# BuckConverter_D14.net
KiCad netlist of a schematic drawn in Altium Designer
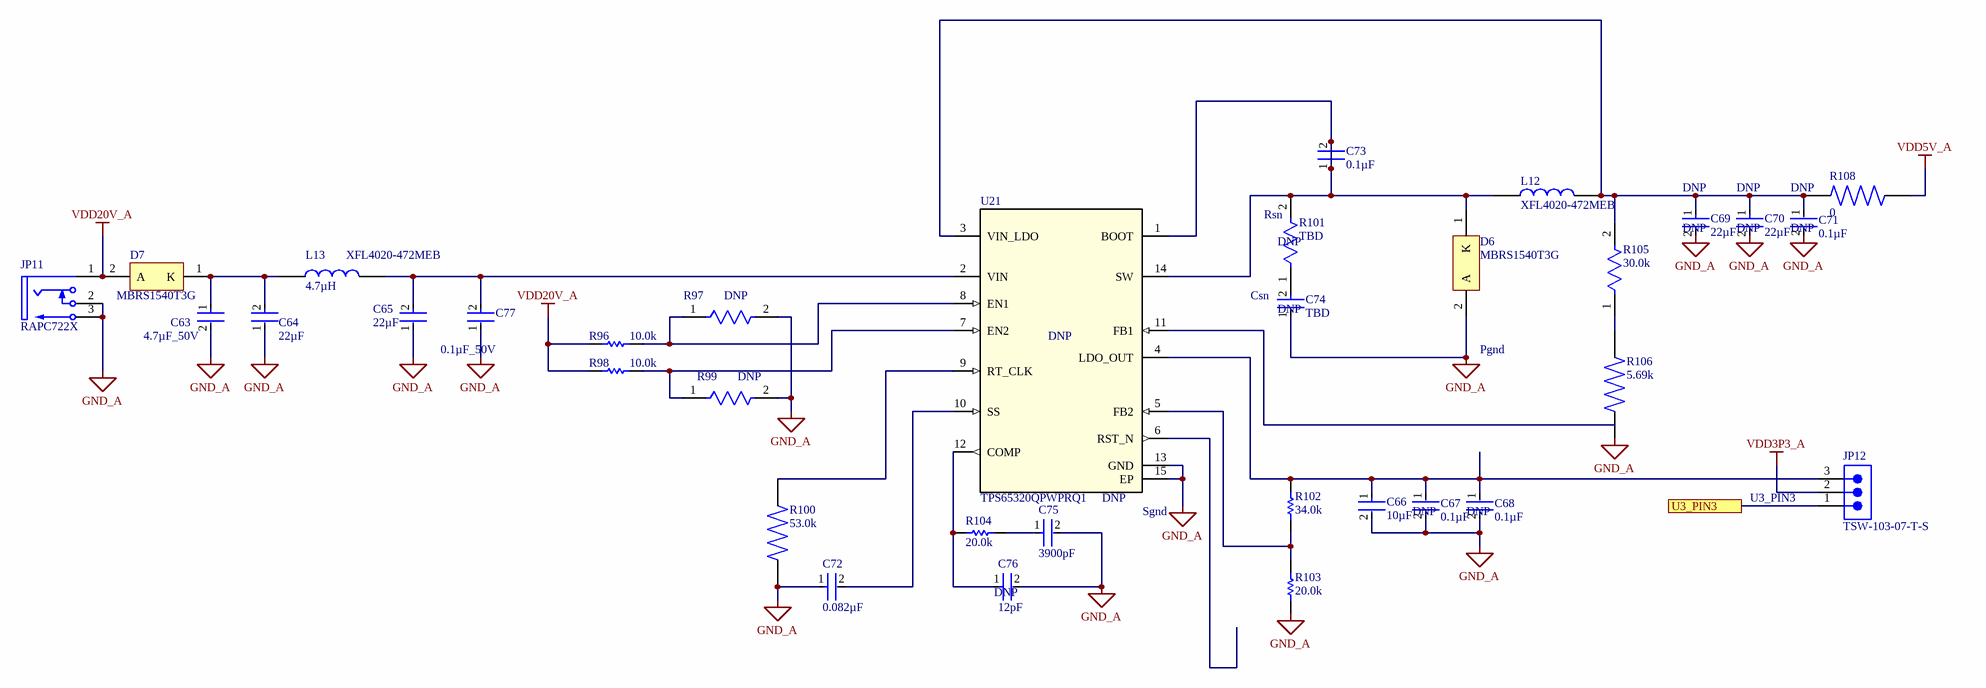
[diagram p0: BuckConverter_D14.SchDoc]

(export (version "E")
  (design (tool "Eeschema 10.0.6"))
  (components
    (comp (ref "C63")
      (value "4.7µF_50V")
      (footprint "FP-C2012-125-0_2-MFG")
      (description "Multilayer Ceramic Capacitors 10μF ±10% 10V X7R SMD 0805")
      (fields (field (name "TOLERANCE") "10%") (field (name "VOLTAGE") "10V"))
      (libsource (lib "Altium Content Vault") (part "b4654b650e69147ec39a6b967a45e02"))
    )
    (comp (ref "C64")
      (value "22µF")
      (footprint "FP-GRM15-MFG")
      (description "CAP CER 0.1UF 16V X7R 0402")
      (fields (field (name "MANUFACTURER PART NUMBER") "GRM155R71C104KA88D") (field (name "TOLERANCE") "10%"))
      (libsource (lib "Altium Content Vault") (part "236180d848d6139a670b325ea6854c9"))
    )
    (comp (ref "C65")
      (value "22µF")
      (footprint "FP-GRM15-MFG")
      (description "CAP CER 0.1UF 16V X7R 0402")
      (fields (field (name "MANUFACTURER PART NUMBER") "GRM155R71C104KA88D") (field (name "TOLERANCE") "10%"))
      (libsource (lib "Altium Content Vault") (part "236180d848d6139a670b325ea6854c9"))
    )
    (comp (ref "C66")
      (value "10µF")
      (footprint "FP-C2012-125-0_2-MFG")
      (description "Multilayer Ceramic Capacitors 10μF ±10% 10V X7R SMD 0805")
      (fields (field (name "TOLERANCE") "10%") (field (name "VOLTAGE") "10V"))
      (libsource (lib "Altium Content Vault") (part "b4654b650e69147ec39a6b967a45e02"))
    )
    (comp (ref "C67")
      (value "0.1µF")
      (footprint "FP-GRM15-MFG")
      (description "CAP CER 0.1UF 16V X7R 0402")
      (fields (field (name "MANUFACTURER PART NUMBER") "GRM155R71C104KA88D") (field (name "TOLERANCE") "10%"))
      (libsource (lib "Altium Content Vault") (part "236180d848d6139a670b325ea6854c9"))
    )
    (comp (ref "C68")
      (value "0.1µF")
      (footprint "FP-GRM15-MFG")
      (description "CAP CER 0.1UF 16V X7R 0402")
      (fields (field (name "MANUFACTURER PART NUMBER") "GRM155R71C104KA88D") (field (name "TOLERANCE") "10%"))
      (libsource (lib "Altium Content Vault") (part "236180d848d6139a670b325ea6854c9"))
    )
    (comp (ref "C69")
      (value "22µF")
      (footprint "FP-C3216-160-0_2-IPC_B")
      (description "Multilayer Ceramic Capacitors 22uF ±20% 25V X5R SMD 1206")
      (fields (field (name "TOLERANCE") "20%"))
      (libsource (lib "Altium Content Vault") (part "11868f565c42a9108669ba33697ecf6"))
    )
    (comp (ref "C70")
      (value "22µF")
      (footprint "FP-C3216-160-0_2-IPC_B")
      (description "Multilayer Ceramic Capacitors 22uF ±20% 25V X5R SMD 1206")
      (fields (field (name "TOLERANCE") "20%"))
      (libsource (lib "Altium Content Vault") (part "11868f565c42a9108669ba33697ecf6"))
    )
    (comp (ref "C71")
      (value "0.1µF")
      (footprint "FP-GRM15-MFG")
      (description "CAP CER 0.1UF 16V X7R 0402")
      (fields (field (name "MANUFACTURER PART NUMBER") "GRM155R71C104KA88D") (field (name "TOLERANCE") "10%"))
      (libsource (lib "Altium Content Vault") (part "236180d848d6139a670b325ea6854c9"))
    )
    (comp (ref "C72")
      (value "0.082µF")
      (footprint "FP-C0402-BB-MFG")
      (description "C0402 82,000 pF X7R 10.00% 16 V")
      (fields
        (field (name "OCTOPART") "https://octopart.com/c0402c823k4ractu-kemet-134782")
        (field (name "MANUFACTURER") "Kemet")
      )
      (libsource (lib "Altium Content Vault") (part "b4654b650e69147ec39a6b967a45e02"))
    )
    (comp (ref "C73")
      (value "0.1µF")
      (footprint "FP-GRM15-MFG")
      (description "CAP CER 0.1UF 16V X7R 0402")
      (fields (field (name "MANUFACTURER PART NUMBER") "GRM155R71C104KA88D") (field (name "TOLERANCE") "10%"))
      (libsource (lib "Altium Content Vault") (part "236180d848d6139a670b325ea6854c9"))
    )
    (comp (ref "C74")
      (value "TBD")
      (footprint "FP-GRM15-MFG")
      (description "CAP CER 0.1UF 16V X7R 0402")
      (fields (field (name "MANUFACTURER PART NUMBER") "GRM155R71C104KA88D") (field (name "TOLERANCE") "10%"))
      (libsource (lib "Altium Content Vault") (part "236180d848d6139a670b325ea6854c9"))
    )
    (comp (ref "C75")
      (value "3900pF")
      (footprint "FP-C0402-BB-MFG")
      (description "CAP CER 3900PF 16V X7R 0402")
      (fields
        (field (name "MANUFACTURER PART NUMBER") "C0402C392K4RACTU")
        (field (name "OCTOPART") "https://octopart.com/c0402c392k4ractu-kemet-12577363")
      )
      (libsource (lib "Altium Content Vault") (part "b4654b650e69147ec39a6b967a45e02"))
    )
    (comp (ref "C76")
      (value "12pF")
      (footprint "FP-C0402-BB-MFG")
      (description "CAP CER 12PF 25V C0G/NP0 0402")
      (fields
        (field (name "OCTOPART") "https://octopart.com/c0402c120j3gacauto-kemet-21768529")
        (field (name "MANUFACTURER PART NUMBER") "C0402C120J3GACAUTO")
      )
      (libsource (lib "Altium Content Vault") (part "b4654b650e69147ec39a6b967a45e02"))
    )
    (comp (ref "C77")
      (value "0.1µF_50V")
      (footprint "FP-C1608-080-0_1-IPC_B")
      (description "Multilayer Ceramic Capacitors 100nF ±10% 50V X7R SMD 0603")
      (fields (field (name "VOLTAGE") "50V") (field (name "TOLERANCE") "10%"))
      (libsource (lib "Altium Content Vault") (part "236180d848d6139a670b325ea6854c9"))
    )
    (comp (ref "D6")
      (value "MBRS1540T3G")
      (footprint "ONSC-SMB-2-403A-03_E_V")
      (description "Schottky Power Rectifier, 2-Pin SMB, Pb-Free, Tape and Reel")
      (fields (field (name "MANUFACTURER") "On Semiconductor"))
      (libsource (lib "") (part "ONSC-D-K1A2-2_A_1"))
    )
    (comp (ref "D7")
      (value "MBRS1540T3G")
      (footprint "ONSC-SMB-2-403A-03_E_V")
      (description "Schottky Power Rectifier, 2-Pin SMB, Pb-Free, Tape and Reel")
      (fields (field (name "MANUFACTURER") "On Semiconductor"))
      (libsource (lib "Altium Content Vault") (part "ONSC-D-K1A2-2_A"))
    )
    (comp (ref "JP11")
      (value "RAPC722X")
      (footprint "SWITCH-RAPC712X-3_V")
      (description "Power Jack, 5 A, 3-Pin THD, RoHS, Bulk")
      (fields (field (name "MANUFACTURER") "Switchcraft"))
      (libsource (lib "Altium Content Vault") (part "SWITCH-RAPC712X-3"))
    )
    (comp (ref "JP12")
      (value "TSW-103-07-T-S")
      (footprint "SMTC-TSW-103-07-X-S")
      (description "0.025\" SQ Post Header, Through-hole, Vertical, -55 to 105 degC, 2.54 mm Pitch, 3-Pin, Male, RoHS")
      (fields (field (name "MANUFACTURER") "Samtec"))
      (libsource (lib "Altium Content Vault") (part "SMTC-TSW-103-X-X-S-X"))
    )
    (comp (ref "L12")
      (value "XFL4020-472MEB")
      (footprint "XFL4020472MEB")
      (description "Fixed Inductors 4.7uH 20% 5A 57.4mOhms AEC-Q200")
      (fields (field (name "MOUSER PART NUMBER") "994-XFL4020-472MEB"))
      (libsource (lib "XFL4020-472MEB") (part "XFL4020-472MEB"))
    )
    (comp (ref "L13")
      (value "4.7µH")
      (footprint "XFL4020472MEB")
      (description "Fixed Inductors 4.7uH 20% 5A 57.4mOhms AEC-Q200")
      (fields
        (field (name "MANUFACTURER_PART_NUMBER") "XFL4020-472MEB")
        (field (name "MOUSER PART NUMBER") "994-XFL4020-472MEB")
      )
      (libsource (lib "XFL4020-472MEB") (part "XFL4020-472MEB"))
    )
    (comp (ref "R96")
      (value "10.0k")
      (footprint "RESC1609X55X30LL15T15")
      (description "Chip Resistor, 10 KOhm, +/- 1%, 0.1 W, -55 to 155 degC, 0603 (1608 Metric), RoHS, Tape and Reel")
      (fields (field (name "TOLERANCE") "1%") (field (name "MANUFACTURER") "Panasonic"))
      (libsource (lib "Altium Content Vault") (part "RES-2"))
    )
    (comp (ref "R97")
      (value "DNP")
      (footprint "FP-ERJ-3GEY0R00V-MFG")
      (description "0 Ohms Jumper 0.1W, 1/10W Chip Resistor 0603 (1608 Metric) Automotive AEC-Q200 Thick Film")
      (fields (field (name "TOLERANCE") "5%"))
      (libsource (lib "Altium Content Vault") (part "1029c3af85768c4190bb7ad29bc67b5"))
    )
    (comp (ref "R98")
      (value "10.0k")
      (footprint "RESC1609X55X30LL15T15")
      (description "Chip Resistor, 10 KOhm, +/- 1%, 0.1 W, -55 to 155 degC, 0603 (1608 Metric), RoHS, Tape and Reel")
      (fields (field (name "TOLERANCE") "1%") (field (name "MANUFACTURER") "Panasonic"))
      (libsource (lib "Altium Content Vault") (part "RES-2"))
    )
    (comp (ref "R99")
      (value "DNP")
      (footprint "FP-ERJ-3GEY0R00V-MFG")
      (description "0 Ohms Jumper 0.1W, 1/10W Chip Resistor 0603 (1608 Metric) Automotive AEC-Q200 Thick Film")
      (fields (field (name "TOLERANCE") "5%"))
      (libsource (lib "Altium Content Vault") (part "1029c3af85768c4190bb7ad29bc67b5"))
    )
    (comp (ref "R100")
      (value "53.0k")
      (footprint "RESC1608X46N:RESC1608X46N")
      (fields (field (name "MP") "PAT0603E5302BST1"))
      (libsource (lib "PAT0603E5302BST1") (part "PAT0603E5302BST1"))
    )
    (comp (ref "R101")
      (value "TBD")
      (footprint "FP-CRCW0603-e3-MFG")
      (description "RES Thick Film, 1kΩ, 1%, 0.1W, 100ppm/°C, 0603")
      (fields (field (name "TOLERANCE") "1%"))
      (libsource (lib "Altium Content Vault") (part "1029c3af85768c4190bb7ad29bc67b5"))
    )
    (comp (ref "R102")
      (value "34.0k")
      (footprint "RESC1608X55X30ML15T15")
      (fields (field (name "PART NUMBER") "ERJ-3EKF3402V") (field (name "MANUFACTURER") "Panasonic"))
      (libsource (lib "Altium Content Vault") (part "RES"))
    )
    (comp (ref "R103")
      (value "20.0k")
      (footprint "RESC1608X55X30ML15T15")
      (fields (field (name "PART NUMBER") "ERJ-3EKF2002V") (field (name "MANUFACTURER") "Panasonic"))
      (libsource (lib "Altium Content Vault") (part "RES"))
    )
    (comp (ref "R104")
      (value "20.0k")
      (footprint "RESC1608X55X30ML15T15")
      (fields (field (name "PART NUMBER") "ERJ-3EKF2002V") (field (name "MANUFACTURER") "Panasonic"))
      (libsource (lib "Altium Content Vault") (part "RES"))
    )
    (comp (ref "R105")
      (value "30.0k")
      (footprint "FP-ERJ3EK-IPC_A")
      (description "RES SMD 30K OHM 1% 1/10W 0603")
      (fields (field (name "TOLERANCE") "1%"))
      (libsource (lib "Altium Content Vault") (part "1029c3af85768c4190bb7ad29bc67b5"))
    )
    (comp (ref "R106")
      (value "5.69k")
      (footprint "RESC1608X46N:RESC1608X46N")
      (fields (field (name "MP") "PAT0603E5691BST1"))
      (libsource (lib "PAT0603E5691BST1") (part "PAT0603E5691BST1"))
    )
    (comp (ref "R108")
      (value "0")
      (footprint "RESC6331X70N")
      (fields (field (name "MF") "Vishay Dale") (field (name "MP") "CRCW25120000Z0EGHP"))
      (libsource (lib "CRCW25120000Z0EGHP") (part "CRCW25120000Z0EGHP"))
    )
    (comp (ref "U21")
      (value "TPS65320QPWPRQ1")
      (footprint "PWP0014E_N")
      (fields
        (field (name "MANUFACTURER") "Texas Instruments")
        (field (name "COPYRIGHT") "Copyright (C) 2025 Ultra Librarian. All rights reserved.")
      )
      (libsource (lib "TPS65320QPWPRQ1") (part "TPS65320QPWPRQ1"))
    )
  )
  (nets
    (net (code "1") (name "/U3_PIN3") (class "Default")
      (node (ref "JP12") (pin "1") (pinfunction "1_1") (pintype "passive"))
    )
    (net (code "2") (name "GND_A") (class "Default")
      (node (ref "C63") (pin "2") (pinfunction "2_2") (pintype "passive"))
      (node (ref "C64") (pin "1") (pinfunction "1_1") (pintype "passive"))
      (node (ref "C65") (pin "1") (pinfunction "1_1") (pintype "passive"))
      (node (ref "C66") (pin "2") (pinfunction "2_2") (pintype "passive"))
      (node (ref "C67") (pin "2") (pinfunction "2_2") (pintype "passive"))
      (node (ref "C68") (pin "2") (pinfunction "2_2") (pintype "passive"))
      (node (ref "C69") (pin "2") (pinfunction "2_2") (pintype "passive"))
      (node (ref "C70") (pin "2") (pinfunction "2_2") (pintype "passive"))
      (node (ref "C71") (pin "2") (pinfunction "2_2") (pintype "passive"))
      (node (ref "C72") (pin "1") (pinfunction "1_1") (pintype "passive"))
      (node (ref "C74") (pin "1") (pinfunction "1_1") (pintype "passive"))
      (node (ref "C75") (pin "2") (pinfunction "2_2") (pintype "passive"))
      (node (ref "C76") (pin "2") (pinfunction "2_2") (pintype "passive"))
      (node (ref "C77") (pin "1") (pinfunction "1_1") (pintype "passive"))
      (node (ref "D6") (pin "2") (pinfunction "A_2") (pintype "passive"))
      (node (ref "JP11") (pin "2") (pinfunction "2_2") (pintype "passive"))
      (node (ref "JP11") (pin "3") (pinfunction "3_3") (pintype "passive"))
      (node (ref "R100") (pin "1") (pinfunction "1_1") (pintype "passive"))
      (node (ref "R103") (pin "1") (pinfunction "1_1") (pintype "passive"))
      (node (ref "R106") (pin "1") (pinfunction "1_1") (pintype "passive"))
      (node (ref "R97") (pin "2") (pinfunction "2_2") (pintype "passive"))
      (node (ref "R99") (pin "2") (pinfunction "2_2") (pintype "passive"))
      (node (ref "U21") (pin "13") (pinfunction "GND_13") (pintype "power_in"))
      (node (ref "U21") (pin "15") (pinfunction "EP_15") (pintype "power_in"))
    )
    (net (code "3") (name "Net-(C74-Pad2)") (class "Default")
      (node (ref "C74") (pin "2") (pinfunction "2_2") (pintype "passive"))
      (node (ref "R101") (pin "1") (pinfunction "1_1") (pintype "passive"))
    )
    (net (code "4") (name "Net-(C75-Pad1)") (class "Default")
      (node (ref "C75") (pin "1") (pinfunction "1_1") (pintype "passive"))
      (node (ref "R104") (pin "2") (pinfunction "2_2") (pintype "passive"))
    )
    (net (code "5") (name "Net-(D6-K)") (class "Default")
      (node (ref "C73") (pin "1") (pinfunction "1_1") (pintype "passive"))
      (node (ref "C73") (pin "2") (pinfunction "2_2") (pintype "passive"))
      (node (ref "D6") (pin "1") (pinfunction "K_1") (pintype "passive"))
      (node (ref "L12") (pin "1") (pinfunction "1_1") (pintype "passive"))
      (node (ref "R101") (pin "2") (pinfunction "2_2") (pintype "passive"))
      (node (ref "U21") (pin "1") (pinfunction "BOOT_1") (pintype "passive"))
      (node (ref "U21") (pin "14") (pinfunction "SW_14") (pintype "power_in"))
    )
    (net (code "6") (name "Net-(D7-K)") (class "Default")
      (node (ref "C63") (pin "1") (pinfunction "1_1") (pintype "passive"))
      (node (ref "C64") (pin "2") (pinfunction "2_2") (pintype "passive"))
      (node (ref "D7") (pin "1") (pinfunction "K_1") (pintype "passive"))
      (node (ref "L13") (pin "1") (pinfunction "1_1") (pintype "passive"))
    )
    (net (code "7") (name "Net-(R105-Pad1)") (class "Default")
      (node (ref "R105") (pin "1") (pinfunction "1_1") (pintype "passive"))
      (node (ref "R106") (pin "2") (pinfunction "2_2") (pintype "passive"))
    )
    (net (code "8") (name "Net-(U21-COMP)") (class "Default")
      (node (ref "C76") (pin "1") (pinfunction "1_1") (pintype "passive"))
      (node (ref "R104") (pin "1") (pinfunction "1_1") (pintype "passive"))
      (node (ref "U21") (pin "12") (pinfunction "COMP_12") (pintype "output"))
    )
    (net (code "9") (name "Net-(U21-EN1)") (class "Default")
      (node (ref "R96") (pin "2") (pinfunction "2_2") (pintype "passive"))
      (node (ref "R97") (pin "1") (pinfunction "1_1") (pintype "passive"))
      (node (ref "U21") (pin "8") (pinfunction "EN1_8") (pintype "input"))
    )
    (net (code "10") (name "Net-(U21-EN2)") (class "Default")
      (node (ref "R98") (pin "2") (pinfunction "2_2") (pintype "passive"))
      (node (ref "R99") (pin "1") (pinfunction "1_1") (pintype "passive"))
      (node (ref "U21") (pin "7") (pinfunction "EN2_7") (pintype "input"))
    )
    (net (code "11") (name "Net-(U21-FB2)") (class "Default")
      (node (ref "R102") (pin "1") (pinfunction "1_1") (pintype "passive"))
      (node (ref "R103") (pin "2") (pinfunction "2_2") (pintype "passive"))
      (node (ref "U21") (pin "5") (pinfunction "FB2_5") (pintype "input"))
    )
    (net (code "12") (name "Net-(U21-LDO_OUT)") (class "Default")
      (node (ref "C66") (pin "1") (pinfunction "1_1") (pintype "passive"))
      (node (ref "C67") (pin "1") (pinfunction "1_1") (pintype "passive"))
      (node (ref "C68") (pin "1") (pinfunction "1_1") (pintype "passive"))
      (node (ref "JP12") (pin "3") (pinfunction "3_3") (pintype "passive"))
      (node (ref "R102") (pin "2") (pinfunction "2_2") (pintype "passive"))
      (node (ref "U21") (pin "4") (pinfunction "LDO_OUT_4") (pintype "power_in"))
    )
    (net (code "13") (name "Net-(U21-RT_CLK)") (class "Default")
      (node (ref "R100") (pin "2") (pinfunction "2_2") (pintype "passive"))
      (node (ref "U21") (pin "9") (pinfunction "RT_CLK_9") (pintype "input"))
    )
    (net (code "14") (name "Net-(U21-SS)") (class "Default")
      (node (ref "C72") (pin "2") (pinfunction "2_2") (pintype "passive"))
      (node (ref "U21") (pin "10") (pinfunction "SS_10") (pintype "input"))
    )
    (net (code "15") (name "Net-(U21-VIN)") (class "Default")
      (node (ref "C65") (pin "2") (pinfunction "2_2") (pintype "passive"))
      (node (ref "C77") (pin "2") (pinfunction "2_2") (pintype "passive"))
      (node (ref "L13") (pin "2") (pinfunction "2_2") (pintype "passive"))
      (node (ref "U21") (pin "2") (pinfunction "VIN_2") (pintype "power_in"))
    )
    (net (code "16") (name "Net-(U21-VIN_LDO)") (class "Default")
      (node (ref "C69") (pin "1") (pinfunction "1_1") (pintype "passive"))
      (node (ref "C70") (pin "1") (pinfunction "1_1") (pintype "passive"))
      (node (ref "C71") (pin "1") (pinfunction "1_1") (pintype "passive"))
      (node (ref "L12") (pin "2") (pinfunction "2_2") (pintype "passive"))
      (node (ref "R105") (pin "2") (pinfunction "2_2") (pintype "passive"))
      (node (ref "R108") (pin "1") (pinfunction "1_1") (pintype "passive"))
      (node (ref "U21") (pin "3") (pinfunction "VIN_LDO_3") (pintype "power_in"))
    )
    (net (code "17") (name "VDD3P3_A") (class "Default")
      (node (ref "JP12") (pin "2") (pinfunction "2_2") (pintype "passive"))
    )
    (net (code "18") (name "VDD5V_A") (class "Default")
      (node (ref "R108") (pin "2") (pinfunction "2_2") (pintype "passive"))
    )
    (net (code "19") (name "VDD20V_A") (class "Default")
      (node (ref "D7") (pin "2") (pinfunction "A_2") (pintype "passive"))
      (node (ref "JP11") (pin "1") (pinfunction "1_1") (pintype "passive"))
      (node (ref "R96") (pin "1") (pinfunction "1_1") (pintype "passive"))
      (node (ref "R98") (pin "1") (pinfunction "1_1") (pintype "passive"))
    )
    (net (code "20") (name "unconnected-(U21-FB1-Pad11)") (class "Default")
      (node (ref "U21") (pin "11") (pinfunction "FB1_11") (pintype "input"))
    )
    (net (code "21") (name "unconnected-(U21-RST_N-Pad6)") (class "Default")
      (node (ref "U21") (pin "6") (pinfunction "RST_N_6") (pintype "output"))
    )
  )
)
